# base.net
KiCad netlist of a schematic drawn in EAGLE
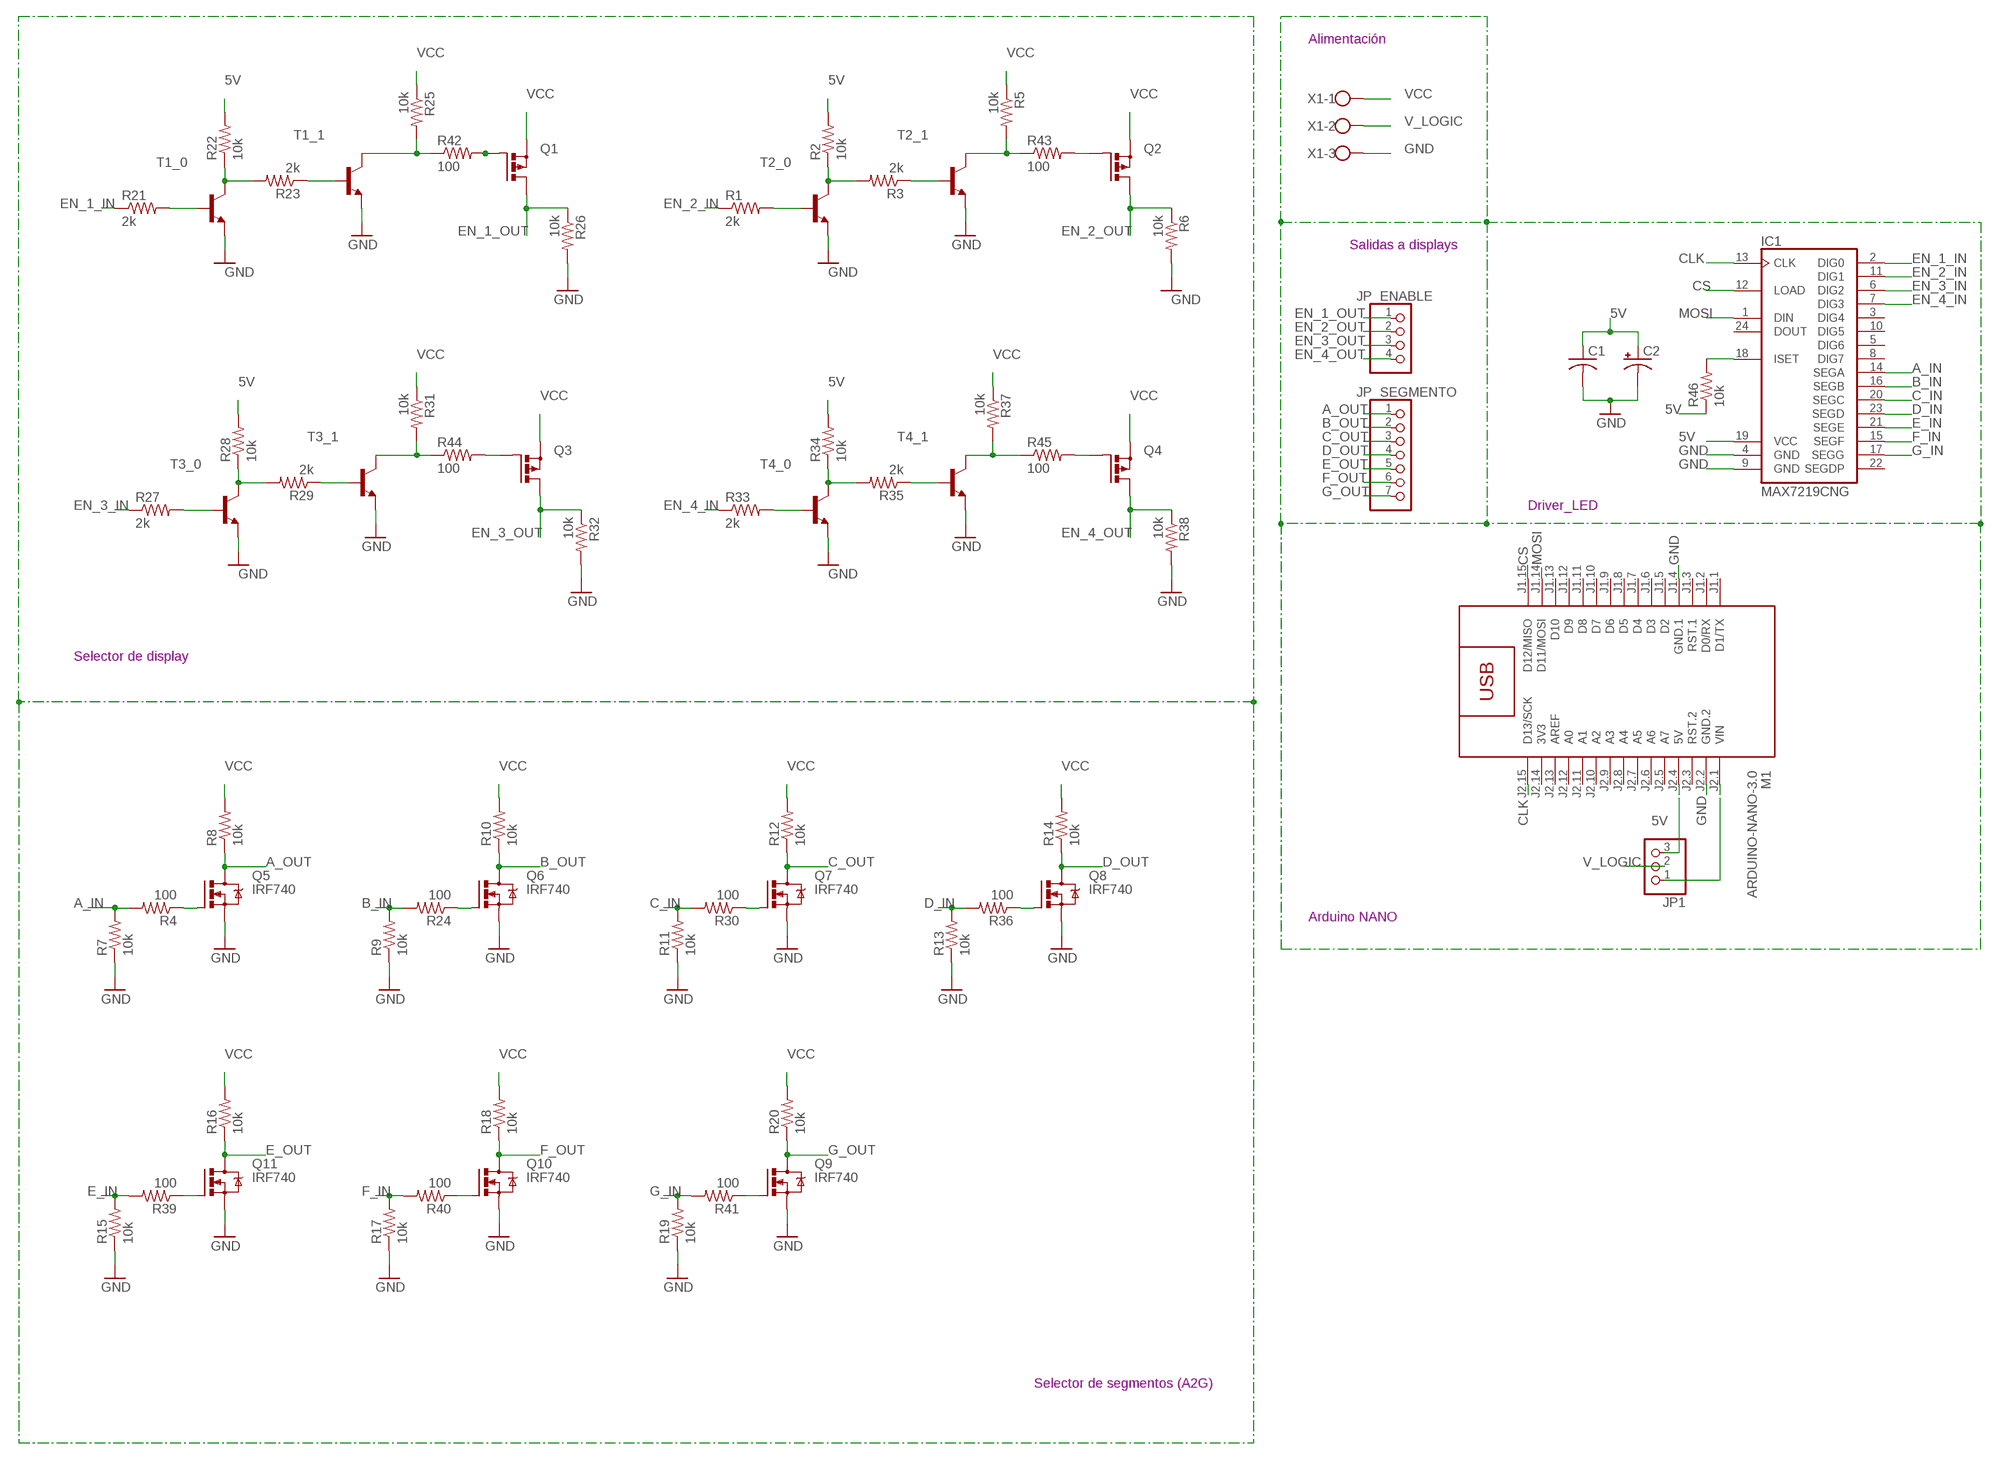
[diagram p0: schematic, sheet 1]

(export (version "E")
  (design (tool "Eeschema 10.0.6"))
  (components
    (comp (ref "C1")
      (value "C-US025-030X050")
      (footprint "eagle-import:C025-030X050")
      (libsource (lib "eagle-import") (part "C-US025-030X050"))
    )
    (comp (ref "C2")
      (value "CPOL-USE2.5-5")
      (footprint "eagle-import:E2,5-5")
      (libsource (lib "eagle-import") (part "CPOL-USE2.5-5"))
    )
    (comp (ref "IC1")
      (value "MAX7219CNG")
      (footprint "eagle-import:DIL24-3")
      (fields (field (name "MF") "MAXIM"))
      (libsource (lib "eagle-import") (part "MAX7219CNG"))
    )
    (comp (ref "JP1")
      (value "PINHD-1X3")
      (footprint "eagle-import:1X03")
      (libsource (lib "eagle-import") (part "PINHD-1X3"))
    )
    (comp (ref "JP_ENABLE")
      (value "PINHD-1X4")
      (footprint "eagle-import:1X04")
      (libsource (lib "eagle-import") (part "PINHD-1X4"))
    )
    (comp (ref "JP_SEGMENTO")
      (value "PINHD-1X7")
      (footprint "eagle-import:1X07")
      (libsource (lib "eagle-import") (part "PINHD-1X7"))
    )
    (comp (ref "M1")
      (value "ARDUINO-NANO-3.0")
      (footprint "eagle-import:ARDUINO-NANO-3.0")
      (libsource (lib "eagle-import") (part "ARDUINO-NANO-3.0"))
    )
    (comp (ref "Q1")
      (value "PMOSFET_PTO220BV")
      (footprint "eagle-import:TO220BV")
      (libsource (lib "eagle-import") (part "PMOSFET_PTO220BV"))
    )
    (comp (ref "Q2")
      (value "PMOSFET_PTO220BV")
      (footprint "eagle-import:TO220BV")
      (libsource (lib "eagle-import") (part "PMOSFET_PTO220BV"))
    )
    (comp (ref "Q3")
      (value "PMOSFET_PTO220BV")
      (footprint "eagle-import:TO220BV")
      (libsource (lib "eagle-import") (part "PMOSFET_PTO220BV"))
    )
    (comp (ref "Q4")
      (value "PMOSFET_PTO220BV")
      (footprint "eagle-import:TO220BV")
      (libsource (lib "eagle-import") (part "PMOSFET_PTO220BV"))
    )
    (comp (ref "Q5")
      (value "IRF740")
      (footprint "eagle-import:TO220BV")
      (libsource (lib "eagle-import") (part "IRF740"))
    )
    (comp (ref "Q6")
      (value "IRF740")
      (footprint "eagle-import:TO220BV")
      (libsource (lib "eagle-import") (part "IRF740"))
    )
    (comp (ref "Q7")
      (value "IRF740")
      (footprint "eagle-import:TO220BV")
      (libsource (lib "eagle-import") (part "IRF740"))
    )
    (comp (ref "Q8")
      (value "IRF740")
      (footprint "eagle-import:TO220BV")
      (libsource (lib "eagle-import") (part "IRF740"))
    )
    (comp (ref "Q9")
      (value "IRF740")
      (footprint "eagle-import:TO220BV")
      (libsource (lib "eagle-import") (part "IRF740"))
    )
    (comp (ref "Q10")
      (value "IRF740")
      (footprint "eagle-import:TO220BV")
      (libsource (lib "eagle-import") (part "IRF740"))
    )
    (comp (ref "Q11")
      (value "IRF740")
      (footprint "eagle-import:TO220BV")
      (libsource (lib "eagle-import") (part "IRF740"))
    )
    (comp (ref "R1")
      (value "2k")
      (footprint "eagle-import:0207_10")
      (libsource (lib "eagle-import") (part "R-US_0207/10"))
    )
    (comp (ref "R2")
      (value "10k")
      (footprint "eagle-import:0207_10")
      (libsource (lib "eagle-import") (part "R-US_0207/10"))
    )
    (comp (ref "R3")
      (value "2k")
      (footprint "eagle-import:0207_10")
      (libsource (lib "eagle-import") (part "R-US_0207/10"))
    )
    (comp (ref "R4")
      (value "100")
      (footprint "eagle-import:0207_10")
      (libsource (lib "eagle-import") (part "R-US_0207/10"))
    )
    (comp (ref "R5")
      (value "10k")
      (footprint "eagle-import:0207_10")
      (libsource (lib "eagle-import") (part "R-US_0207/10"))
    )
    (comp (ref "R6")
      (value "10k")
      (footprint "eagle-import:0207_10")
      (libsource (lib "eagle-import") (part "R-US_0207/10"))
    )
    (comp (ref "R7")
      (value "10k")
      (footprint "eagle-import:0207_10")
      (libsource (lib "eagle-import") (part "R-US_0207/10"))
    )
    (comp (ref "R8")
      (value "10k")
      (footprint "eagle-import:0207_10")
      (libsource (lib "eagle-import") (part "R-US_0207/10"))
    )
    (comp (ref "R9")
      (value "10k")
      (footprint "eagle-import:0207_10")
      (libsource (lib "eagle-import") (part "R-US_0207/10"))
    )
    (comp (ref "R10")
      (value "10k")
      (footprint "eagle-import:0207_10")
      (libsource (lib "eagle-import") (part "R-US_0207/10"))
    )
    (comp (ref "R11")
      (value "10k")
      (footprint "eagle-import:0207_10")
      (libsource (lib "eagle-import") (part "R-US_0207/10"))
    )
    (comp (ref "R12")
      (value "10k")
      (footprint "eagle-import:0207_10")
      (libsource (lib "eagle-import") (part "R-US_0207/10"))
    )
    (comp (ref "R13")
      (value "10k")
      (footprint "eagle-import:0207_10")
      (libsource (lib "eagle-import") (part "R-US_0207/10"))
    )
    (comp (ref "R14")
      (value "10k")
      (footprint "eagle-import:0207_10")
      (libsource (lib "eagle-import") (part "R-US_0207/10"))
    )
    (comp (ref "R15")
      (value "10k")
      (footprint "eagle-import:0207_10")
      (libsource (lib "eagle-import") (part "R-US_0207/10"))
    )
    (comp (ref "R16")
      (value "10k")
      (footprint "eagle-import:0207_10")
      (libsource (lib "eagle-import") (part "R-US_0207/10"))
    )
    (comp (ref "R17")
      (value "10k")
      (footprint "eagle-import:0207_10")
      (libsource (lib "eagle-import") (part "R-US_0207/10"))
    )
    (comp (ref "R18")
      (value "10k")
      (footprint "eagle-import:0207_10")
      (libsource (lib "eagle-import") (part "R-US_0207/10"))
    )
    (comp (ref "R19")
      (value "10k")
      (footprint "eagle-import:0207_10")
      (libsource (lib "eagle-import") (part "R-US_0207/10"))
    )
    (comp (ref "R20")
      (value "10k")
      (footprint "eagle-import:0207_10")
      (libsource (lib "eagle-import") (part "R-US_0207/10"))
    )
    (comp (ref "R21")
      (value "2k")
      (footprint "eagle-import:0207_10")
      (libsource (lib "eagle-import") (part "R-US_0207/10"))
    )
    (comp (ref "R22")
      (value "10k")
      (footprint "eagle-import:0207_10")
      (libsource (lib "eagle-import") (part "R-US_0207/10"))
    )
    (comp (ref "R23")
      (value "2k")
      (footprint "eagle-import:0207_10")
      (libsource (lib "eagle-import") (part "R-US_0207/10"))
    )
    (comp (ref "R24")
      (value "100")
      (footprint "eagle-import:0207_10")
      (libsource (lib "eagle-import") (part "R-US_0207/10"))
    )
    (comp (ref "R25")
      (value "10k")
      (footprint "eagle-import:0207_10")
      (libsource (lib "eagle-import") (part "R-US_0207/10"))
    )
    (comp (ref "R26")
      (value "10k")
      (footprint "eagle-import:0207_10")
      (libsource (lib "eagle-import") (part "R-US_0207/10"))
    )
    (comp (ref "R27")
      (value "2k")
      (footprint "eagle-import:0207_10")
      (libsource (lib "eagle-import") (part "R-US_0207/10"))
    )
    (comp (ref "R28")
      (value "10k")
      (footprint "eagle-import:0207_10")
      (libsource (lib "eagle-import") (part "R-US_0207/10"))
    )
    (comp (ref "R29")
      (value "2k")
      (footprint "eagle-import:0207_10")
      (libsource (lib "eagle-import") (part "R-US_0207/10"))
    )
    (comp (ref "R30")
      (value "100")
      (footprint "eagle-import:0207_10")
      (libsource (lib "eagle-import") (part "R-US_0207/10"))
    )
    (comp (ref "R31")
      (value "10k")
      (footprint "eagle-import:0207_10")
      (libsource (lib "eagle-import") (part "R-US_0207/10"))
    )
    (comp (ref "R32")
      (value "10k")
      (footprint "eagle-import:0207_10")
      (libsource (lib "eagle-import") (part "R-US_0207/10"))
    )
    (comp (ref "R33")
      (value "2k")
      (footprint "eagle-import:0207_10")
      (libsource (lib "eagle-import") (part "R-US_0207/10"))
    )
    (comp (ref "R34")
      (value "10k")
      (footprint "eagle-import:0207_10")
      (libsource (lib "eagle-import") (part "R-US_0207/10"))
    )
    (comp (ref "R35")
      (value "2k")
      (footprint "eagle-import:0207_10")
      (libsource (lib "eagle-import") (part "R-US_0207/10"))
    )
    (comp (ref "R36")
      (value "100")
      (footprint "eagle-import:0207_10")
      (libsource (lib "eagle-import") (part "R-US_0207/10"))
    )
    (comp (ref "R37")
      (value "10k")
      (footprint "eagle-import:0207_10")
      (libsource (lib "eagle-import") (part "R-US_0207/10"))
    )
    (comp (ref "R38")
      (value "10k")
      (footprint "eagle-import:0207_10")
      (libsource (lib "eagle-import") (part "R-US_0207/10"))
    )
    (comp (ref "R39")
      (value "100")
      (footprint "eagle-import:0207_10")
      (libsource (lib "eagle-import") (part "R-US_0207/10"))
    )
    (comp (ref "R40")
      (value "100")
      (footprint "eagle-import:0207_10")
      (libsource (lib "eagle-import") (part "R-US_0207/10"))
    )
    (comp (ref "R41")
      (value "100")
      (footprint "eagle-import:0207_10")
      (libsource (lib "eagle-import") (part "R-US_0207/10"))
    )
    (comp (ref "R42")
      (value "100")
      (footprint "eagle-import:0207_10")
      (libsource (lib "eagle-import") (part "R-US_0207/10"))
    )
    (comp (ref "R43")
      (value "100")
      (footprint "eagle-import:0207_10")
      (libsource (lib "eagle-import") (part "R-US_0207/10"))
    )
    (comp (ref "R44")
      (value "100")
      (footprint "eagle-import:0207_10")
      (libsource (lib "eagle-import") (part "R-US_0207/10"))
    )
    (comp (ref "R45")
      (value "100")
      (footprint "eagle-import:0207_10")
      (libsource (lib "eagle-import") (part "R-US_0207/10"))
    )
    (comp (ref "R46")
      (value "10k")
      (footprint "eagle-import:0207_10")
      (libsource (lib "eagle-import") (part "R-US_0207/10"))
    )
    (comp (ref "T1_0")
      (value "2N2222-NPN-TO92-EBC")
      (footprint "eagle-import:TO92-EBC")
      (libsource (lib "eagle-import") (part "-NPN-TO92-EBC2N2222"))
    )
    (comp (ref "T1_1")
      (value "2N2222-NPN-TO92-EBC")
      (footprint "eagle-import:TO92-EBC")
      (libsource (lib "eagle-import") (part "-NPN-TO92-EBC2N2222"))
    )
    (comp (ref "T2_0")
      (value "2N2222-NPN-TO92-EBC")
      (footprint "eagle-import:TO92-EBC")
      (libsource (lib "eagle-import") (part "-NPN-TO92-EBC2N2222"))
    )
    (comp (ref "T2_1")
      (value "2N2222-NPN-TO92-EBC")
      (footprint "eagle-import:TO92-EBC")
      (libsource (lib "eagle-import") (part "-NPN-TO92-EBC2N2222"))
    )
    (comp (ref "T3_0")
      (value "2N2222-NPN-TO92-EBC")
      (footprint "eagle-import:TO92-EBC")
      (libsource (lib "eagle-import") (part "-NPN-TO92-EBC2N2222"))
    )
    (comp (ref "T3_1")
      (value "2N2222-NPN-TO92-EBC")
      (footprint "eagle-import:TO92-EBC")
      (libsource (lib "eagle-import") (part "-NPN-TO92-EBC2N2222"))
    )
    (comp (ref "T4_0")
      (value "2N2222-NPN-TO92-EBC")
      (footprint "eagle-import:TO92-EBC")
      (libsource (lib "eagle-import") (part "-NPN-TO92-EBC2N2222"))
    )
    (comp (ref "T4_1")
      (value "2N2222-NPN-TO92-EBC")
      (footprint "eagle-import:TO92-EBC")
      (libsource (lib "eagle-import") (part "-NPN-TO92-EBC2N2222"))
    )
    (comp (ref "X1")
      (value "W237-103")
      (footprint "eagle-import:W237-103")
      (fields (field (name "MPN") "237-103"))
      (libsource (lib "eagle-import") (part "W237-103"))
    )
  )
  (nets
    (net (code "1") (name "/3V3") (class "Default")
      (node (ref "M1") (pin "J2.14") (pinfunction "3V3_J2.14") (pintype "power_in"))
    )
    (net (code "2") (name "/5V") (class "Default")
      (node (ref "C1") (pin "1") (pinfunction "1_1") (pintype "passive"))
      (node (ref "C2") (pin "+") (pinfunction "+_+") (pintype "passive"))
      (node (ref "IC1") (pin "19") (pinfunction "VCC_19") (pintype "power_in"))
      (node (ref "JP1") (pin "3") (pinfunction "3_3") (pintype "passive"))
      (node (ref "M1") (pin "J2.4") (pinfunction "5V_J2.4") (pintype "power_in"))
      (node (ref "R2") (pin "2") (pinfunction "2_2") (pintype "passive"))
      (node (ref "R22") (pin "2") (pinfunction "2_2") (pintype "passive"))
      (node (ref "R28") (pin "2") (pinfunction "2_2") (pintype "passive"))
      (node (ref "R34") (pin "2") (pinfunction "2_2") (pintype "passive"))
      (node (ref "R46") (pin "1") (pinfunction "1_1") (pintype "passive"))
    )
    (net (code "3") (name "/A_IN") (class "Default")
      (node (ref "IC1") (pin "14") (pinfunction "SEGA_14") (pintype "output"))
      (node (ref "R4") (pin "2") (pinfunction "2_2") (pintype "passive"))
      (node (ref "R7") (pin "2") (pinfunction "2_2") (pintype "passive"))
    )
    (net (code "4") (name "/A_OUT") (class "Default")
      (node (ref "JP_SEGMENTO") (pin "1") (pinfunction "1_1") (pintype "passive"))
      (node (ref "Q5") (pin "D") (pinfunction "D_D") (pintype "passive"))
      (node (ref "R8") (pin "1") (pinfunction "1_1") (pintype "passive"))
    )
    (net (code "5") (name "/B_IN") (class "Default")
      (node (ref "IC1") (pin "16") (pinfunction "SEGB_16") (pintype "output"))
      (node (ref "R24") (pin "2") (pinfunction "2_2") (pintype "passive"))
      (node (ref "R9") (pin "2") (pinfunction "2_2") (pintype "passive"))
    )
    (net (code "6") (name "/B_OUT") (class "Default")
      (node (ref "JP_SEGMENTO") (pin "2") (pinfunction "2_2") (pintype "passive"))
      (node (ref "Q6") (pin "D") (pinfunction "D_D") (pintype "passive"))
      (node (ref "R10") (pin "1") (pinfunction "1_1") (pintype "passive"))
    )
    (net (code "7") (name "/CLK") (class "Default")
      (node (ref "IC1") (pin "13") (pinfunction "CLK_13") (pintype "input"))
      (node (ref "M1") (pin "J2.15") (pinfunction "D13/SCK_J2.15") (pintype "bidirectional"))
    )
    (net (code "8") (name "/CS") (class "Default")
      (node (ref "IC1") (pin "12") (pinfunction "LOAD_12") (pintype "input"))
      (node (ref "M1") (pin "J1.15") (pinfunction "D12/MISO_J1.15") (pintype "bidirectional"))
    )
    (net (code "9") (name "/C_IN") (class "Default")
      (node (ref "IC1") (pin "20") (pinfunction "SEGC_20") (pintype "output"))
      (node (ref "R11") (pin "2") (pinfunction "2_2") (pintype "passive"))
      (node (ref "R30") (pin "2") (pinfunction "2_2") (pintype "passive"))
    )
    (net (code "10") (name "/C_OUT") (class "Default")
      (node (ref "JP_SEGMENTO") (pin "3") (pinfunction "3_3") (pintype "passive"))
      (node (ref "Q7") (pin "D") (pinfunction "D_D") (pintype "passive"))
      (node (ref "R12") (pin "1") (pinfunction "1_1") (pintype "passive"))
    )
    (net (code "11") (name "/D_IN") (class "Default")
      (node (ref "IC1") (pin "23") (pinfunction "SEGD_23") (pintype "output"))
      (node (ref "R13") (pin "2") (pinfunction "2_2") (pintype "passive"))
      (node (ref "R36") (pin "2") (pinfunction "2_2") (pintype "passive"))
    )
    (net (code "12") (name "/D_OUT") (class "Default")
      (node (ref "JP_SEGMENTO") (pin "4") (pinfunction "4_4") (pintype "passive"))
      (node (ref "Q8") (pin "D") (pinfunction "D_D") (pintype "passive"))
      (node (ref "R14") (pin "1") (pinfunction "1_1") (pintype "passive"))
    )
    (net (code "13") (name "/EN_1_IN") (class "Default")
      (node (ref "IC1") (pin "2") (pinfunction "DIG0_2") (pintype "output"))
      (node (ref "R21") (pin "1") (pinfunction "1_1") (pintype "passive"))
    )
    (net (code "14") (name "/EN_1_OUT") (class "Default")
      (node (ref "JP_ENABLE") (pin "1") (pinfunction "1_1") (pintype "passive"))
      (node (ref "Q1") (pin "D") (pinfunction "D_D") (pintype "passive"))
      (node (ref "R26") (pin "1") (pinfunction "1_1") (pintype "passive"))
    )
    (net (code "15") (name "/EN_2_IN") (class "Default")
      (node (ref "IC1") (pin "11") (pinfunction "DIG1_11") (pintype "output"))
      (node (ref "R1") (pin "1") (pinfunction "1_1") (pintype "passive"))
    )
    (net (code "16") (name "/EN_2_OUT") (class "Default")
      (node (ref "JP_ENABLE") (pin "2") (pinfunction "2_2") (pintype "passive"))
      (node (ref "Q2") (pin "D") (pinfunction "D_D") (pintype "passive"))
      (node (ref "R6") (pin "1") (pinfunction "1_1") (pintype "passive"))
    )
    (net (code "17") (name "/EN_3_IN") (class "Default")
      (node (ref "IC1") (pin "6") (pinfunction "DIG2_6") (pintype "output"))
      (node (ref "R27") (pin "1") (pinfunction "1_1") (pintype "passive"))
    )
    (net (code "18") (name "/EN_3_OUT") (class "Default")
      (node (ref "JP_ENABLE") (pin "3") (pinfunction "3_3") (pintype "passive"))
      (node (ref "Q3") (pin "D") (pinfunction "D_D") (pintype "passive"))
      (node (ref "R32") (pin "1") (pinfunction "1_1") (pintype "passive"))
    )
    (net (code "19") (name "/EN_4_IN") (class "Default")
      (node (ref "IC1") (pin "7") (pinfunction "DIG3_7") (pintype "output"))
      (node (ref "R33") (pin "1") (pinfunction "1_1") (pintype "passive"))
    )
    (net (code "20") (name "/EN_4_OUT") (class "Default")
      (node (ref "JP_ENABLE") (pin "4") (pinfunction "4_4") (pintype "passive"))
      (node (ref "Q4") (pin "D") (pinfunction "D_D") (pintype "passive"))
      (node (ref "R38") (pin "1") (pinfunction "1_1") (pintype "passive"))
    )
    (net (code "21") (name "/E_IN") (class "Default")
      (node (ref "IC1") (pin "21") (pinfunction "SEGE_21") (pintype "output"))
      (node (ref "R15") (pin "2") (pinfunction "2_2") (pintype "passive"))
      (node (ref "R39") (pin "2") (pinfunction "2_2") (pintype "passive"))
    )
    (net (code "22") (name "/E_OUT") (class "Default")
      (node (ref "JP_SEGMENTO") (pin "5") (pinfunction "5_5") (pintype "passive"))
      (node (ref "Q11") (pin "D") (pinfunction "D_D") (pintype "passive"))
      (node (ref "R16") (pin "1") (pinfunction "1_1") (pintype "passive"))
    )
    (net (code "23") (name "/F_IN") (class "Default")
      (node (ref "IC1") (pin "15") (pinfunction "SEGF_15") (pintype "output"))
      (node (ref "R17") (pin "2") (pinfunction "2_2") (pintype "passive"))
      (node (ref "R40") (pin "2") (pinfunction "2_2") (pintype "passive"))
    )
    (net (code "24") (name "/F_OUT") (class "Default")
      (node (ref "JP_SEGMENTO") (pin "6") (pinfunction "6_6") (pintype "passive"))
      (node (ref "Q10") (pin "D") (pinfunction "D_D") (pintype "passive"))
      (node (ref "R18") (pin "1") (pinfunction "1_1") (pintype "passive"))
    )
    (net (code "25") (name "/G_IN") (class "Default")
      (node (ref "IC1") (pin "17") (pinfunction "SEGG_17") (pintype "output"))
      (node (ref "R19") (pin "2") (pinfunction "2_2") (pintype "passive"))
      (node (ref "R41") (pin "2") (pinfunction "2_2") (pintype "passive"))
    )
    (net (code "26") (name "/G_OUT") (class "Default")
      (node (ref "JP_SEGMENTO") (pin "7") (pinfunction "7_7") (pintype "passive"))
      (node (ref "Q9") (pin "D") (pinfunction "D_D") (pintype "passive"))
      (node (ref "R20") (pin "1") (pinfunction "1_1") (pintype "passive"))
    )
    (net (code "27") (name "/MOSI") (class "Default")
      (node (ref "IC1") (pin "1") (pinfunction "DIN_1") (pintype "input"))
      (node (ref "M1") (pin "J1.14") (pinfunction "D11/MOSI_J1.14") (pintype "bidirectional"))
    )
    (net (code "28") (name "/VCC") (class "Default")
      (node (ref "Q1") (pin "S") (pinfunction "S_S") (pintype "passive"))
      (node (ref "Q2") (pin "S") (pinfunction "S_S") (pintype "passive"))
      (node (ref "Q3") (pin "S") (pinfunction "S_S") (pintype "passive"))
      (node (ref "Q4") (pin "S") (pinfunction "S_S") (pintype "passive"))
      (node (ref "R10") (pin "2") (pinfunction "2_2") (pintype "passive"))
      (node (ref "R12") (pin "2") (pinfunction "2_2") (pintype "passive"))
      (node (ref "R14") (pin "2") (pinfunction "2_2") (pintype "passive"))
      (node (ref "R16") (pin "2") (pinfunction "2_2") (pintype "passive"))
      (node (ref "R18") (pin "2") (pinfunction "2_2") (pintype "passive"))
      (node (ref "R20") (pin "2") (pinfunction "2_2") (pintype "passive"))
      (node (ref "R25") (pin "1") (pinfunction "1_1") (pintype "passive"))
      (node (ref "R31") (pin "1") (pinfunction "1_1") (pintype "passive"))
      (node (ref "R37") (pin "1") (pinfunction "1_1") (pintype "passive"))
      (node (ref "R5") (pin "1") (pinfunction "1_1") (pintype "passive"))
      (node (ref "R8") (pin "2") (pinfunction "2_2") (pintype "passive"))
      (node (ref "X1") (pin "1") (pinfunction "KL_1") (pintype "passive"))
    )
    (net (code "29") (name "/V_LOGIC") (class "Default")
      (node (ref "JP1") (pin "2") (pinfunction "2_2") (pintype "passive"))
      (node (ref "X1") (pin "2") (pinfunction "KL_2") (pintype "passive"))
    )
    (net (code "30") (name "GND") (class "Default")
      (node (ref "C1") (pin "2") (pinfunction "2_2") (pintype "passive"))
      (node (ref "C2") (pin "-") (pinfunction "-_-") (pintype "passive"))
      (node (ref "IC1") (pin "4") (pinfunction "GND_4") (pintype "power_in"))
      (node (ref "IC1") (pin "9") (pinfunction "GND_9") (pintype "power_in"))
      (node (ref "M1") (pin "J1.4") (pinfunction "GND.1_J1.4") (pintype "power_in"))
      (node (ref "M1") (pin "J2.2") (pinfunction "GND.2_J2.2") (pintype "power_in"))
      (node (ref "Q10") (pin "S") (pinfunction "S_S") (pintype "passive"))
      (node (ref "Q11") (pin "S") (pinfunction "S_S") (pintype "passive"))
      (node (ref "Q5") (pin "S") (pinfunction "S_S") (pintype "passive"))
      (node (ref "Q6") (pin "S") (pinfunction "S_S") (pintype "passive"))
      (node (ref "Q7") (pin "S") (pinfunction "S_S") (pintype "passive"))
      (node (ref "Q8") (pin "S") (pinfunction "S_S") (pintype "passive"))
      (node (ref "Q9") (pin "S") (pinfunction "S_S") (pintype "passive"))
      (node (ref "R11") (pin "1") (pinfunction "1_1") (pintype "passive"))
      (node (ref "R13") (pin "1") (pinfunction "1_1") (pintype "passive"))
      (node (ref "R15") (pin "1") (pinfunction "1_1") (pintype "passive"))
      (node (ref "R17") (pin "1") (pinfunction "1_1") (pintype "passive"))
      (node (ref "R19") (pin "1") (pinfunction "1_1") (pintype "passive"))
      (node (ref "R26") (pin "2") (pinfunction "2_2") (pintype "passive"))
      (node (ref "R32") (pin "2") (pinfunction "2_2") (pintype "passive"))
      (node (ref "R38") (pin "2") (pinfunction "2_2") (pintype "passive"))
      (node (ref "R6") (pin "2") (pinfunction "2_2") (pintype "passive"))
      (node (ref "R7") (pin "1") (pinfunction "1_1") (pintype "passive"))
      (node (ref "R9") (pin "1") (pinfunction "1_1") (pintype "passive"))
      (node (ref "T1_0") (pin "E") (pinfunction "E_E") (pintype "passive"))
      (node (ref "T1_1") (pin "E") (pinfunction "E_E") (pintype "passive"))
      (node (ref "T2_0") (pin "E") (pinfunction "E_E") (pintype "passive"))
      (node (ref "T2_1") (pin "E") (pinfunction "E_E") (pintype "passive"))
      (node (ref "T3_0") (pin "E") (pinfunction "E_E") (pintype "passive"))
      (node (ref "T3_1") (pin "E") (pinfunction "E_E") (pintype "passive"))
      (node (ref "T4_0") (pin "E") (pinfunction "E_E") (pintype "passive"))
      (node (ref "T4_1") (pin "E") (pinfunction "E_E") (pintype "passive"))
      (node (ref "X1") (pin "3") (pinfunction "KL_3") (pintype "passive"))
    )
    (net (code "31") (name "Net-(IC1-ISET)") (class "Default")
      (node (ref "IC1") (pin "18") (pinfunction "ISET_18") (pintype "input"))
      (node (ref "R46") (pin "2") (pinfunction "2_2") (pintype "passive"))
    )
    (net (code "32") (name "Net-(M1-VIN)") (class "Default")
      (node (ref "JP1") (pin "1") (pinfunction "1_1") (pintype "passive"))
      (node (ref "M1") (pin "J2.1") (pinfunction "VIN_J2.1") (pintype "power_in"))
    )
    (net (code "33") (name "Net-(Q1-PadG)") (class "Default")
      (node (ref "Q1") (pin "G") (pinfunction "G_G") (pintype "passive"))
      (node (ref "R42") (pin "2") (pinfunction "2_2") (pintype "passive"))
    )
    (net (code "34") (name "Net-(Q2-PadG)") (class "Default")
      (node (ref "Q2") (pin "G") (pinfunction "G_G") (pintype "passive"))
      (node (ref "R43") (pin "2") (pinfunction "2_2") (pintype "passive"))
    )
    (net (code "35") (name "Net-(Q3-PadG)") (class "Default")
      (node (ref "Q3") (pin "G") (pinfunction "G_G") (pintype "passive"))
      (node (ref "R44") (pin "2") (pinfunction "2_2") (pintype "passive"))
    )
    (net (code "36") (name "Net-(Q4-PadG)") (class "Default")
      (node (ref "Q4") (pin "G") (pinfunction "G_G") (pintype "passive"))
      (node (ref "R45") (pin "2") (pinfunction "2_2") (pintype "passive"))
    )
    (net (code "37") (name "Net-(Q5-PadG)") (class "Default")
      (node (ref "Q5") (pin "G") (pinfunction "G_G") (pintype "passive"))
      (node (ref "R4") (pin "1") (pinfunction "1_1") (pintype "passive"))
    )
    (net (code "38") (name "Net-(Q6-PadG)") (class "Default")
      (node (ref "Q6") (pin "G") (pinfunction "G_G") (pintype "passive"))
      (node (ref "R24") (pin "1") (pinfunction "1_1") (pintype "passive"))
    )
    (net (code "39") (name "Net-(Q7-PadG)") (class "Default")
      (node (ref "Q7") (pin "G") (pinfunction "G_G") (pintype "passive"))
      (node (ref "R30") (pin "1") (pinfunction "1_1") (pintype "passive"))
    )
    (net (code "40") (name "Net-(Q8-PadG)") (class "Default")
      (node (ref "Q8") (pin "G") (pinfunction "G_G") (pintype "passive"))
      (node (ref "R36") (pin "1") (pinfunction "1_1") (pintype "passive"))
    )
    (net (code "41") (name "Net-(Q9-PadG)") (class "Default")
      (node (ref "Q9") (pin "G") (pinfunction "G_G") (pintype "passive"))
      (node (ref "R41") (pin "1") (pinfunction "1_1") (pintype "passive"))
    )
    (net (code "42") (name "Net-(Q10-PadG)") (class "Default")
      (node (ref "Q10") (pin "G") (pinfunction "G_G") (pintype "passive"))
      (node (ref "R40") (pin "1") (pinfunction "1_1") (pintype "passive"))
    )
    (net (code "43") (name "Net-(Q11-PadG)") (class "Default")
      (node (ref "Q11") (pin "G") (pinfunction "G_G") (pintype "passive"))
      (node (ref "R39") (pin "1") (pinfunction "1_1") (pintype "passive"))
    )
    (net (code "44") (name "Net-(R1-Pad2)") (class "Default")
      (node (ref "R1") (pin "2") (pinfunction "2_2") (pintype "passive"))
      (node (ref "T2_0") (pin "B") (pinfunction "B_B") (pintype "passive"))
    )
    (net (code "45") (name "Net-(R2-Pad1)") (class "Default")
      (node (ref "R2") (pin "1") (pinfunction "1_1") (pintype "passive"))
      (node (ref "R3") (pin "2") (pinfunction "2_2") (pintype "passive"))
      (node (ref "T2_0") (pin "C") (pinfunction "C_C") (pintype "passive"))
    )
    (net (code "46") (name "Net-(R3-Pad1)") (class "Default")
      (node (ref "R3") (pin "1") (pinfunction "1_1") (pintype "passive"))
      (node (ref "T2_1") (pin "B") (pinfunction "B_B") (pintype "passive"))
    )
    (net (code "47") (name "Net-(R21-Pad2)") (class "Default")
      (node (ref "R21") (pin "2") (pinfunction "2_2") (pintype "passive"))
      (node (ref "T1_0") (pin "B") (pinfunction "B_B") (pintype "passive"))
    )
    (net (code "48") (name "Net-(R22-Pad1)") (class "Default")
      (node (ref "R22") (pin "1") (pinfunction "1_1") (pintype "passive"))
      (node (ref "R23") (pin "2") (pinfunction "2_2") (pintype "passive"))
      (node (ref "T1_0") (pin "C") (pinfunction "C_C") (pintype "passive"))
    )
    (net (code "49") (name "Net-(R23-Pad1)") (class "Default")
      (node (ref "R23") (pin "1") (pinfunction "1_1") (pintype "passive"))
      (node (ref "T1_1") (pin "B") (pinfunction "B_B") (pintype "passive"))
    )
    (net (code "50") (name "Net-(R25-Pad2)") (class "Default")
      (node (ref "R25") (pin "2") (pinfunction "2_2") (pintype "passive"))
      (node (ref "R42") (pin "1") (pinfunction "1_1") (pintype "passive"))
      (node (ref "T1_1") (pin "C") (pinfunction "C_C") (pintype "passive"))
    )
    (net (code "51") (name "Net-(R27-Pad2)") (class "Default")
      (node (ref "R27") (pin "2") (pinfunction "2_2") (pintype "passive"))
      (node (ref "T3_0") (pin "B") (pinfunction "B_B") (pintype "passive"))
    )
    (net (code "52") (name "Net-(R28-Pad1)") (class "Default")
      (node (ref "R28") (pin "1") (pinfunction "1_1") (pintype "passive"))
      (node (ref "R29") (pin "2") (pinfunction "2_2") (pintype "passive"))
      (node (ref "T3_0") (pin "C") (pinfunction "C_C") (pintype "passive"))
    )
    (net (code "53") (name "Net-(R29-Pad1)") (class "Default")
      (node (ref "R29") (pin "1") (pinfunction "1_1") (pintype "passive"))
      (node (ref "T3_1") (pin "B") (pinfunction "B_B") (pintype "passive"))
    )
    (net (code "54") (name "Net-(R31-Pad2)") (class "Default")
      (node (ref "R31") (pin "2") (pinfunction "2_2") (pintype "passive"))
      (node (ref "R44") (pin "1") (pinfunction "1_1") (pintype "passive"))
      (node (ref "T3_1") (pin "C") (pinfunction "C_C") (pintype "passive"))
    )
    (net (code "55") (name "Net-(R33-Pad2)") (class "Default")
      (node (ref "R33") (pin "2") (pinfunction "2_2") (pintype "passive"))
      (node (ref "T4_0") (pin "B") (pinfunction "B_B") (pintype "passive"))
    )
    (net (code "56") (name "Net-(R34-Pad1)") (class "Default")
      (node (ref "R34") (pin "1") (pinfunction "1_1") (pintype "passive"))
      (node (ref "R35") (pin "2") (pinfunction "2_2") (pintype "passive"))
      (node (ref "T4_0") (pin "C") (pinfunction "C_C") (pintype "passive"))
    )
    (net (code "57") (name "Net-(R35-Pad1)") (class "Default")
      (node (ref "R35") (pin "1") (pinfunction "1_1") (pintype "passive"))
      (node (ref "T4_1") (pin "B") (pinfunction "B_B") (pintype "passive"))
    )
    (net (code "58") (name "Net-(R37-Pad2)") (class "Default")
      (node (ref "R37") (pin "2") (pinfunction "2_2") (pintype "passive"))
      (node (ref "R45") (pin "1") (pinfunction "1_1") (pintype "passive"))
      (node (ref "T4_1") (pin "C") (pinfunction "C_C") (pintype "passive"))
    )
    (net (code "59") (name "Net-(R43-Pad1)") (class "Default")
      (node (ref "R43") (pin "1") (pinfunction "1_1") (pintype "passive"))
      (node (ref "R5") (pin "2") (pinfunction "2_2") (pintype "passive"))
      (node (ref "T2_1") (pin "C") (pinfunction "C_C") (pintype "passive"))
    )
    (net (code "60") (name "unconnected-(IC1-DIG4-Pad3)") (class "Default")
      (node (ref "IC1") (pin "3") (pinfunction "DIG4_3") (pintype "output"))
    )
    (net (code "61") (name "unconnected-(IC1-DIG5-Pad10)") (class "Default")
      (node (ref "IC1") (pin "10") (pinfunction "DIG5_10") (pintype "output"))
    )
    (net (code "62") (name "unconnected-(IC1-DIG6-Pad5)") (class "Default")
      (node (ref "IC1") (pin "5") (pinfunction "DIG6_5") (pintype "output"))
    )
    (net (code "63") (name "unconnected-(IC1-DIG7-Pad8)") (class "Default")
      (node (ref "IC1") (pin "8") (pinfunction "DIG7_8") (pintype "output"))
    )
    (net (code "64") (name "unconnected-(IC1-DOUT-Pad24)") (class "Default")
      (node (ref "IC1") (pin "24") (pinfunction "DOUT_24") (pintype "output"))
    )
    (net (code "65") (name "unconnected-(IC1-SEGDP-Pad22)") (class "Default")
      (node (ref "IC1") (pin "22") (pinfunction "SEGDP_22") (pintype "output"))
    )
    (net (code "66") (name "unconnected-(M1-A0-PadJ2.12)") (class "Default")
      (node (ref "M1") (pin "J2.12") (pinfunction "A0_J2.12") (pintype "bidirectional"))
    )
    (net (code "67") (name "unconnected-(M1-A1-PadJ2.11)") (class "Default")
      (node (ref "M1") (pin "J2.11") (pinfunction "A1_J2.11") (pintype "bidirectional"))
    )
    (net (code "68") (name "unconnected-(M1-A2-PadJ2.10)") (class "Default")
      (node (ref "M1") (pin "J2.10") (pinfunction "A2_J2.10") (pintype "bidirectional"))
    )
    (net (code "69") (name "unconnected-(M1-A3-PadJ2.9)") (class "Default")
      (node (ref "M1") (pin "J2.9") (pinfunction "A3_J2.9") (pintype "bidirectional"))
    )
    (net (code "70") (name "unconnected-(M1-A4-PadJ2.8)") (class "Default")
      (node (ref "M1") (pin "J2.8") (pinfunction "A4_J2.8") (pintype "bidirectional"))
    )
    (net (code "71") (name "unconnected-(M1-A5-PadJ2.7)") (class "Default")
      (node (ref "M1") (pin "J2.7") (pinfunction "A5_J2.7") (pintype "bidirectional"))
    )
    (net (code "72") (name "unconnected-(M1-A6-PadJ2.6)") (class "Default")
      (node (ref "M1") (pin "J2.6") (pinfunction "A6_J2.6") (pintype "bidirectional"))
    )
    (net (code "73") (name "unconnected-(M1-A7-PadJ2.5)") (class "Default")
      (node (ref "M1") (pin "J2.5") (pinfunction "A7_J2.5") (pintype "bidirectional"))
    )
    (net (code "74") (name "unconnected-(M1-AREF-PadJ2.13)") (class "Default")
      (node (ref "M1") (pin "J2.13") (pinfunction "AREF_J2.13") (pintype "bidirectional"))
    )
    (net (code "75") (name "unconnected-(M1-D0{slash}RX-PadJ1.2)") (class "Default")
      (node (ref "M1") (pin "J1.2") (pinfunction "D0/RX_J1.2") (pintype "bidirectional"))
    )
    (net (code "76") (name "unconnected-(M1-D1{slash}TX-PadJ1.1)") (class "Default")
      (node (ref "M1") (pin "J1.1") (pinfunction "D1/TX_J1.1") (pintype "bidirectional"))
    )
    (net (code "77") (name "unconnected-(M1-D2-PadJ1.5)") (class "Default")
      (node (ref "M1") (pin "J1.5") (pinfunction "D2_J1.5") (pintype "bidirectional"))
    )
    (net (code "78") (name "unconnected-(M1-D3-PadJ1.6)") (class "Default")
      (node (ref "M1") (pin "J1.6") (pinfunction "D3_J1.6") (pintype "bidirectional"))
    )
    (net (code "79") (name "unconnected-(M1-D4-PadJ1.7)") (class "Default")
      (node (ref "M1") (pin "J1.7") (pinfunction "D4_J1.7") (pintype "bidirectional"))
    )
    (net (code "80") (name "unconnected-(M1-D5-PadJ1.8)") (class "Default")
      (node (ref "M1") (pin "J1.8") (pinfunction "D5_J1.8") (pintype "bidirectional"))
    )
    (net (code "81") (name "unconnected-(M1-D6-PadJ1.9)") (class "Default")
      (node (ref "M1") (pin "J1.9") (pinfunction "D6_J1.9") (pintype "bidirectional"))
    )
    (net (code "82") (name "unconnected-(M1-D7-PadJ1.10)") (class "Default")
      (node (ref "M1") (pin "J1.10") (pinfunction "D7_J1.10") (pintype "bidirectional"))
    )
    (net (code "83") (name "unconnected-(M1-D8-PadJ1.11)") (class "Default")
      (node (ref "M1") (pin "J1.11") (pinfunction "D8_J1.11") (pintype "bidirectional"))
    )
    (net (code "84") (name "unconnected-(M1-D9-PadJ1.12)") (class "Default")
      (node (ref "M1") (pin "J1.12") (pinfunction "D9_J1.12") (pintype "bidirectional"))
    )
    (net (code "85") (name "unconnected-(M1-D10-PadJ1.13)") (class "Default")
      (node (ref "M1") (pin "J1.13") (pinfunction "D10_J1.13") (pintype "bidirectional"))
    )
    (net (code "86") (name "unconnected-(M1-RST.1-PadJ1.3)") (class "Default")
      (node (ref "M1") (pin "J1.3") (pinfunction "RST.1_J1.3") (pintype "bidirectional"))
    )
    (net (code "87") (name "unconnected-(M1-RST.2-PadJ2.3)") (class "Default")
      (node (ref "M1") (pin "J2.3") (pinfunction "RST.2_J2.3") (pintype "bidirectional"))
    )
  )
)
